# overtemp_indicator.net
KiCad netlist of a schematic drawn in Altium Designer
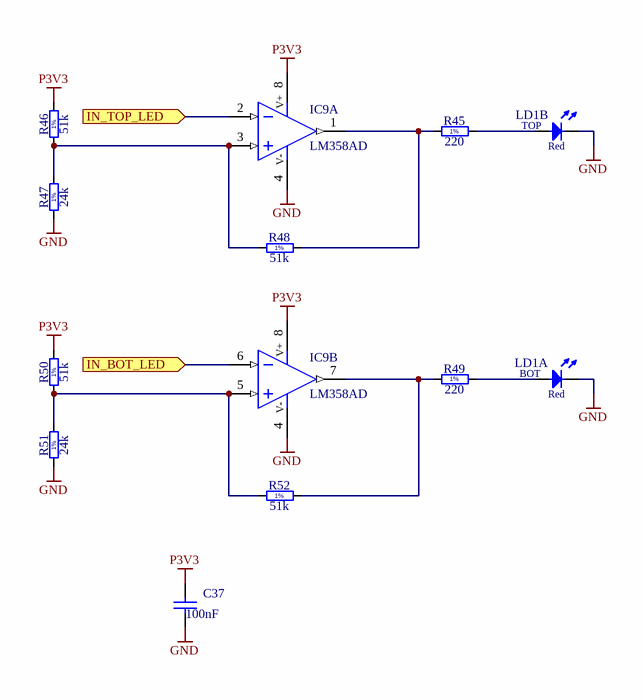
[diagram p0: overtemp_indicator.SchDoc]

(export (version "E")
  (design (tool "Eeschema 10.0.6"))
  (components
    (comp (ref "C37")
      (value "100nF")
      (footprint "CAPC1005X55N")
      (description "Non-polarised capacitor")
      (fields
        (field (name "PART NUMBER") "CC0402_100NF_16V_10%_X5R")
        (field (name "VOLTAGE") "16V")
        (field (name "AUTHOR") "CERN DEM JLC")
      )
      (libsource (lib "Capacitors") (part "Capacitor - non polarized"))
    )
    (comp (ref "IC9")
      (value "LM358AD")
      (footprint "SOIC127P600X175-8N")
      (description "Dual Operational Amplifier")
      (fields (field (name "MANUFACTURER") "TEXAS INSTRUMENTS") (field (name "AUTHOR") "CERN DEM JLC"))
      (libsource (lib "ICs And Semiconductors") (part "Operational Amplifier x2 Type1"))
    )
    (comp (ref "LD1")
      (value "Red/Red")
      (footprint "LED_DIALIGHT_571-0111F")
      (description "LED x2 Red 1C2A-BOT_3C4A-TOP")
      (fields
        (field (name "PART NUMBER") "LED_DIALIGHT_571-0111F")
        (field (name "MANUFACTURER") "DIALIGHT")
        (field (name "AUTHOR") "CERN DEM JLC")
      )
      (libsource (lib "ICs And Semiconductors") (part "LED x2 Red 1C2A-BOT_3C4A-TOP"))
    )
    (comp (ref "R45")
      (value "220")
      (footprint "RESC1608X55N")
      (description "Resistor - 1%")
      (fields
        (field (name "PART NUMBER") "R0603_220R_1%_0.1W_100PPM")
        (field (name "POWER") "0.1W")
        (field (name "AUTHOR") "CERN DEM JLC")
      )
      (libsource (lib "Resistors") (part "Resistor - 1%"))
    )
    (comp (ref "R46")
      (value "51k")
      (footprint "RESC1608X55N")
      (description "Resistor - 1%")
      (fields
        (field (name "PART NUMBER") "R0603_51K_1%_0.1W_100PPM")
        (field (name "POWER") "0.1W")
        (field (name "AUTHOR") "CERN DEM JLC")
      )
      (libsource (lib "Resistors") (part "Resistor - 1%"))
    )
    (comp (ref "R47")
      (value "24k")
      (footprint "RESC1608X55N")
      (description "Resistor - 1%")
      (fields
        (field (name "PART NUMBER") "R0603_24K_1%_0.1W_100PPM")
        (field (name "POWER") "0.1W")
        (field (name "AUTHOR") "CERN DEM JLC")
      )
      (libsource (lib "Resistors") (part "Resistor - 1%"))
    )
    (comp (ref "R48")
      (value "51k")
      (footprint "RESC1608X55N")
      (description "Resistor - 1%")
      (fields
        (field (name "PART NUMBER") "R0603_51K_1%_0.1W_100PPM")
        (field (name "POWER") "0.1W")
        (field (name "AUTHOR") "CERN DEM JLC")
      )
      (libsource (lib "Resistors") (part "Resistor - 1%"))
    )
    (comp (ref "R49")
      (value "220")
      (footprint "RESC1608X55N")
      (description "Resistor - 1%")
      (fields
        (field (name "PART NUMBER") "R0603_220R_1%_0.1W_100PPM")
        (field (name "POWER") "0.1W")
        (field (name "AUTHOR") "CERN DEM JLC")
      )
      (libsource (lib "Resistors") (part "Resistor - 1%"))
    )
    (comp (ref "R50")
      (value "51k")
      (footprint "RESC1608X55N")
      (description "Resistor - 1%")
      (fields
        (field (name "PART NUMBER") "R0603_51K_1%_0.1W_100PPM")
        (field (name "POWER") "0.1W")
        (field (name "AUTHOR") "CERN DEM JLC")
      )
      (libsource (lib "Resistors") (part "Resistor - 1%"))
    )
    (comp (ref "R51")
      (value "24k")
      (footprint "RESC1608X55N")
      (description "Resistor - 1%")
      (fields
        (field (name "PART NUMBER") "R0603_24K_1%_0.1W_100PPM")
        (field (name "POWER") "0.1W")
        (field (name "AUTHOR") "CERN DEM JLC")
      )
      (libsource (lib "Resistors") (part "Resistor - 1%"))
    )
    (comp (ref "R52")
      (value "51k")
      (footprint "RESC1608X55N")
      (description "Resistor - 1%")
      (fields
        (field (name "PART NUMBER") "R0603_51K_1%_0.1W_100PPM")
        (field (name "POWER") "0.1W")
        (field (name "AUTHOR") "CERN DEM JLC")
      )
      (libsource (lib "Resistors") (part "Resistor - 1%"))
    )
  )
  (nets
    (net (code "1") (name "/IN_BOT_LED") (class "Default")
      (node (ref "IC9") (pin "6") (pinfunction "IN-_6") (pintype "input"))
    )
    (net (code "2") (name "/IN_TOP_LED") (class "Default")
      (node (ref "IC9") (pin "2") (pinfunction "IN-_2") (pintype "input"))
    )
    (net (code "3") (name "GND") (class "Default")
      (node (ref "C37") (pin "1") (pinfunction "1_1") (pintype "passive"))
      (node (ref "IC9") (pin "4") (pinfunction "V-_4") (pintype "power_in"))
      (node (ref "LD1") (pin "1") (pinfunction "C_1") (pintype "passive"))
      (node (ref "LD1") (pin "3") (pinfunction "C_3") (pintype "passive"))
      (node (ref "R47") (pin "1") (pinfunction "1_1") (pintype "passive"))
      (node (ref "R51") (pin "1") (pinfunction "1_1") (pintype "passive"))
    )
    (net (code "4") (name "Net-(IC9A-IN+)") (class "Default")
      (node (ref "IC9") (pin "3") (pinfunction "IN+_3") (pintype "input"))
      (node (ref "R46") (pin "1") (pinfunction "1_1") (pintype "passive"))
      (node (ref "R47") (pin "2") (pinfunction "2_2") (pintype "passive"))
      (node (ref "R48") (pin "1") (pinfunction "1_1") (pintype "passive"))
    )
    (net (code "5") (name "Net-(IC9A-OUT)") (class "Default")
      (node (ref "IC9") (pin "1") (pinfunction "OUT_1") (pintype "output"))
      (node (ref "R45") (pin "1") (pinfunction "1_1") (pintype "passive"))
      (node (ref "R48") (pin "2") (pinfunction "2_2") (pintype "passive"))
    )
    (net (code "6") (name "Net-(IC9B-IN+)") (class "Default")
      (node (ref "IC9") (pin "5") (pinfunction "IN+_5") (pintype "input"))
      (node (ref "R50") (pin "1") (pinfunction "1_1") (pintype "passive"))
      (node (ref "R51") (pin "2") (pinfunction "2_2") (pintype "passive"))
      (node (ref "R52") (pin "1") (pinfunction "1_1") (pintype "passive"))
    )
    (net (code "7") (name "Net-(IC9B-OUT)") (class "Default")
      (node (ref "IC9") (pin "7") (pinfunction "OUT_7") (pintype "output"))
      (node (ref "R49") (pin "1") (pinfunction "1_1") (pintype "passive"))
      (node (ref "R52") (pin "2") (pinfunction "2_2") (pintype "passive"))
    )
    (net (code "8") (name "Net-(LD1A-A)") (class "Default")
      (node (ref "LD1") (pin "2") (pinfunction "A_2") (pintype "passive"))
      (node (ref "R49") (pin "2") (pinfunction "2_2") (pintype "passive"))
    )
    (net (code "9") (name "Net-(LD1B-A)") (class "Default")
      (node (ref "LD1") (pin "4") (pinfunction "A_4") (pintype "passive"))
      (node (ref "R45") (pin "2") (pinfunction "2_2") (pintype "passive"))
    )
    (net (code "10") (name "P3V3") (class "Default")
      (node (ref "C37") (pin "2") (pinfunction "2_2") (pintype "passive"))
      (node (ref "IC9") (pin "8") (pinfunction "V+_8") (pintype "power_in"))
      (node (ref "R46") (pin "2") (pinfunction "2_2") (pintype "passive"))
      (node (ref "R50") (pin "2") (pinfunction "2_2") (pintype "passive"))
    )
  )
)
